# Power_micro_v3.net
KiCad netlist of a schematic drawn in Altium Designer
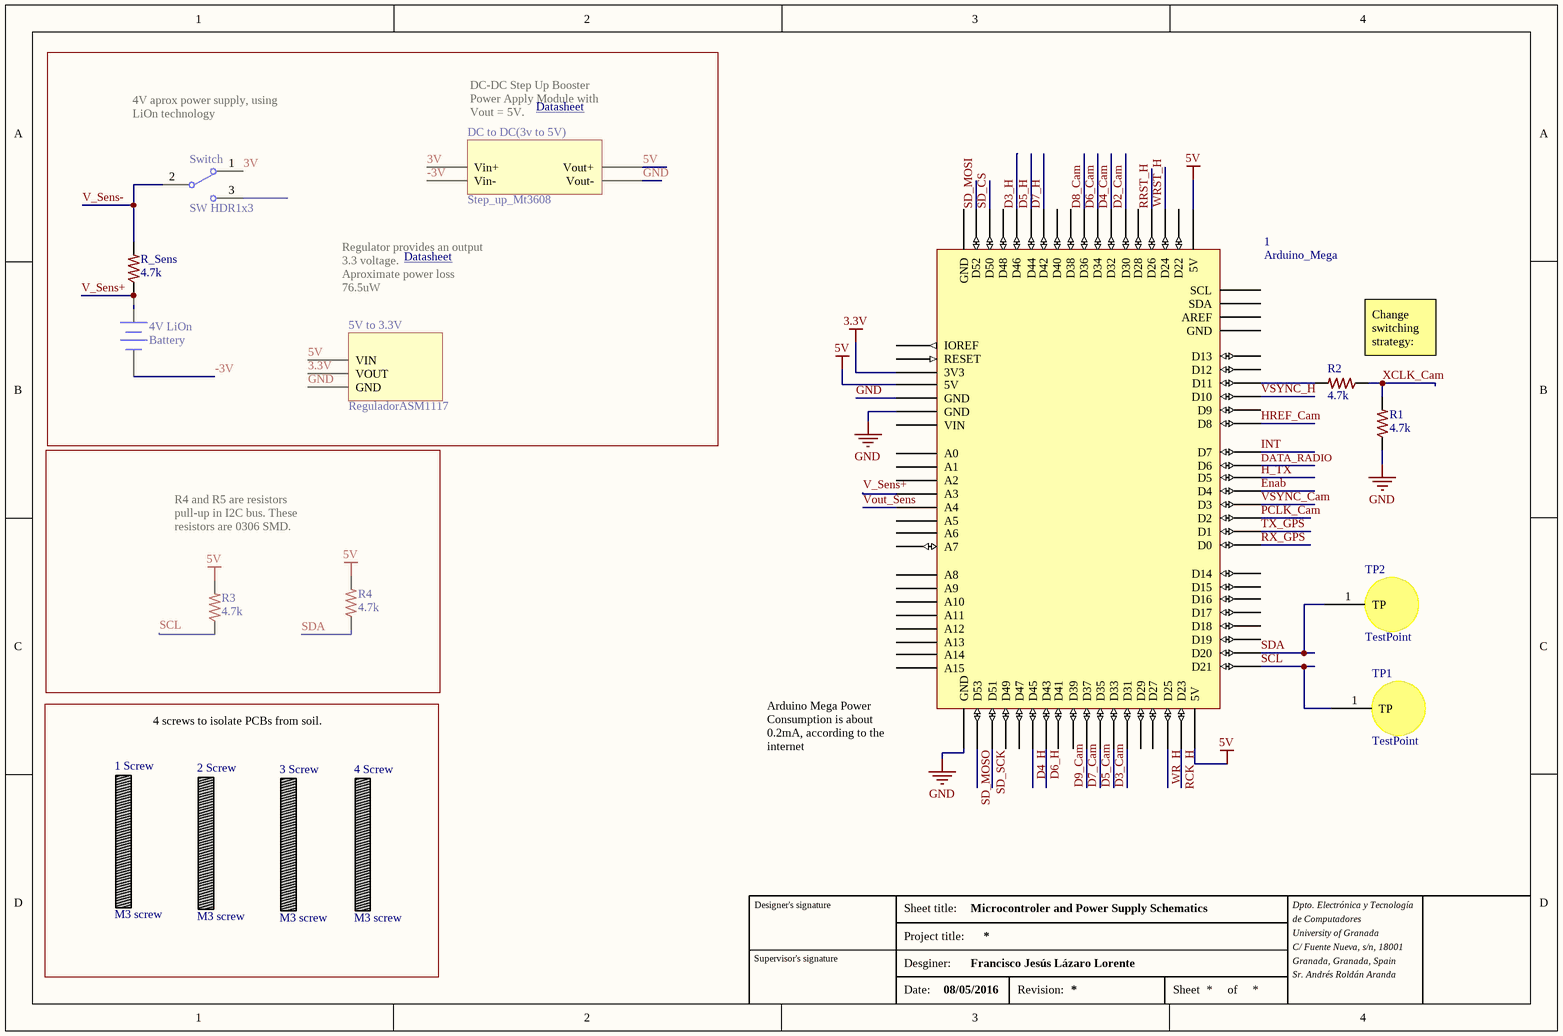
[diagram p0: Power_micro_v3.SchDoc]

(export (version "E")
  (design (tool "Eeschema 10.0.6"))
  (components
    (comp (ref "1")
      (value "Arduino_Mega")
      (footprint "Footprint-ArduinoMega-headers - named")
      (libsource (lib "Trackuino_Shield") (part "Arduino_Mega"))
    )
    (comp (ref "1 Screw")
      (value "M3 screw")
      (footprint "M3Screw")
      (libsource (lib "Schlib1") (part "M3 screw"))
    )
    (comp (ref "2 Screw")
      (value "M3 screw")
      (footprint "M3Screw")
      (libsource (lib "Schlib1") (part "M3 screw"))
    )
    (comp (ref "3 Screw")
      (value "M3 screw")
      (footprint "M3Screw")
      (libsource (lib "Schlib1") (part "M3 screw"))
    )
    (comp (ref "4 Screw")
      (value "M3 screw")
      (footprint "M3Screw")
      (libsource (lib "Schlib1") (part "M3 screw"))
    )
    (comp (ref "4V LiOn")
      (value "Battery")
      (footprint "BAT-2 - duplicate")
      (description "Multicell Battery")
      (fields (field (name "PUBLISHER") "Altium Limited"))
      (libsource (lib "Trackuino_Shield") (part "Battery"))
    )
    (comp (ref "5V to 3.3V")
      (value "ReguladorASM1117")
      (footprint "1X03 - ReguladorASM1117 - horizontal")
      (libsource (lib "Trackuino_Shield") (part "ReguladorASM1117"))
    )
    (comp (ref "DC to DC(3v to 5V)")
      (value "Step_up_Mt3608")
      (footprint "Step_up_Mt3608")
      (libsource (lib "Trackuino_Shield") (part "Step_up_Mt3608"))
    )
    (comp (ref "R1")
      (value "4.7k")
      (footprint "0805")
      (libsource (lib "Trackuino_Shield") (part "0805RESISTOR"))
    )
    (comp (ref "R2")
      (value "4.7k")
      (footprint "0805")
      (libsource (lib "Trackuino_Shield") (part "0805RESISTOR"))
    )
    (comp (ref "R3")
      (value "4.7k")
      (footprint "0805")
      (libsource (lib "Trackuino_Shield") (part "0805RESISTOR"))
    )
    (comp (ref "R4")
      (value "4.7k")
      (footprint "0805")
      (libsource (lib "Trackuino_Shield") (part "0805RESISTOR"))
    )
    (comp (ref "R_Sens")
      (value "4.7k")
      (footprint "0805")
      (libsource (lib "Trackuino_Shield") (part "0805RESISTOR"))
    )
    (comp (ref "Switch")
      (value "SW HDR1x3")
      (footprint "SWITCH3x1")
      (libsource (lib "Trackuino_Shield") (part "SW HDR1x3"))
    )
    (comp (ref "TP1")
      (value "TestPoint")
      (footprint "TestPoint")
      (libsource (lib "Trackuino_Shield") (part "TestPoint"))
    )
    (comp (ref "TP2")
      (value "TestPoint")
      (footprint "TestPoint")
      (libsource (lib "Trackuino_Shield") (part "TestPoint"))
    )
  )
  (nets
    (net (code "1") (name "/-3V") (class "Default")
      (node (ref "4V LiOn") (pin "GND") (pinfunction "-_GND") (pintype "passive"))
      (node (ref "DC to DC(3v to 5V)") (pin "VIN-") (pinfunction "Vin-_VIN-") (pintype "passive"))
    )
    (net (code "2") (name "/3V") (class "Default")
      (node (ref "DC to DC(3v to 5V)") (pin "VIN+") (pinfunction "Vin+_VIN+") (pintype "passive"))
      (node (ref "Switch") (pin "1") (pinfunction "NC1_1") (pintype "passive"))
    )
    (net (code "3") (name "/D2_Cam") (class "Default")
      (node (ref "1") (pin "D30") (pinfunction "D30_D30") (pintype "bidirectional"))
    )
    (net (code "4") (name "/D3_Cam") (class "Default")
      (node (ref "1") (pin "D31") (pinfunction "D31_D31") (pintype "bidirectional"))
    )
    (net (code "5") (name "/D3_H") (class "Default")
      (node (ref "1") (pin "D46") (pinfunction "D46_D46") (pintype "bidirectional"))
    )
    (net (code "6") (name "/D4_Cam") (class "Default")
      (node (ref "1") (pin "D32") (pinfunction "D32_D32") (pintype "bidirectional"))
    )
    (net (code "7") (name "/D4_H") (class "Default")
      (node (ref "1") (pin "D45") (pinfunction "D45_D45") (pintype "bidirectional"))
    )
    (net (code "8") (name "/D5_Cam") (class "Default")
      (node (ref "1") (pin "D33") (pinfunction "D33_D33") (pintype "bidirectional"))
    )
    (net (code "9") (name "/D5_H") (class "Default")
      (node (ref "1") (pin "D44") (pinfunction "D44_D44") (pintype "bidirectional"))
    )
    (net (code "10") (name "/D6_Cam") (class "Default")
      (node (ref "1") (pin "D34") (pinfunction "D34_D34") (pintype "bidirectional"))
    )
    (net (code "11") (name "/D6_H") (class "Default")
      (node (ref "1") (pin "D43") (pinfunction "D43_D43") (pintype "bidirectional"))
    )
    (net (code "12") (name "/D7_Cam") (class "Default")
      (node (ref "1") (pin "D35") (pinfunction "D35_D35") (pintype "bidirectional"))
    )
    (net (code "13") (name "/D7_H") (class "Default")
      (node (ref "1") (pin "D42") (pinfunction "D42_D42") (pintype "bidirectional"))
    )
    (net (code "14") (name "/D8_Cam") (class "Default")
      (node (ref "1") (pin "D36") (pinfunction "D36_D36") (pintype "bidirectional"))
    )
    (net (code "15") (name "/D9_Cam") (class "Default")
      (node (ref "1") (pin "D37") (pinfunction "D37_D37") (pintype "bidirectional"))
    )
    (net (code "16") (name "/DATA_RADIO") (class "Default")
      (node (ref "1") (pin "D6") (pinfunction "D6_D6") (pintype "bidirectional"))
    )
    (net (code "17") (name "/Enab") (class "Default")
      (node (ref "1") (pin "D4") (pinfunction "D4_D4") (pintype "bidirectional"))
    )
    (net (code "18") (name "/HREF_Cam") (class "Default")
      (node (ref "1") (pin "D8") (pinfunction "D8_D8") (pintype "bidirectional"))
    )
    (net (code "19") (name "/H_TX") (class "Default")
      (node (ref "1") (pin "D5") (pinfunction "D5_D5") (pintype "bidirectional"))
    )
    (net (code "20") (name "/INT") (class "Default")
      (node (ref "1") (pin "D7") (pinfunction "D7_D7") (pintype "bidirectional"))
    )
    (net (code "21") (name "/PCLK_Cam") (class "Default")
      (node (ref "1") (pin "D2") (pinfunction "D2_D2") (pintype "bidirectional"))
    )
    (net (code "22") (name "/RCK_H") (class "Default")
      (node (ref "1") (pin "D23") (pinfunction "D23_D23") (pintype "bidirectional"))
    )
    (net (code "23") (name "/RRST_H") (class "Default")
      (node (ref "1") (pin "D26") (pinfunction "D26_D26") (pintype "bidirectional"))
    )
    (net (code "24") (name "/RX_GPS") (class "Default")
      (node (ref "1") (pin "D0") (pinfunction "D0_D0") (pintype "bidirectional"))
    )
    (net (code "25") (name "/SCL") (class "Default")
      (node (ref "1") (pin "D21") (pinfunction "D21_D21") (pintype "bidirectional"))
      (node (ref "R3") (pin "1") (pinfunction "1_1") (pintype "passive"))
      (node (ref "TP1") (pin "1") (pinfunction "TP_1") (pintype "passive"))
    )
    (net (code "26") (name "/SDA") (class "Default")
      (node (ref "1") (pin "D20") (pinfunction "D20_D20") (pintype "bidirectional"))
      (node (ref "R4") (pin "1") (pinfunction "1_1") (pintype "passive"))
      (node (ref "TP2") (pin "1") (pinfunction "TP_1") (pintype "passive"))
    )
    (net (code "27") (name "/SD_CS") (class "Default")
      (node (ref "1") (pin "D50") (pinfunction "D50_D50") (pintype "bidirectional"))
    )
    (net (code "28") (name "/SD_MOSI") (class "Default")
      (node (ref "1") (pin "D52") (pinfunction "D52_D52") (pintype "bidirectional"))
    )
    (net (code "29") (name "/SD_MOSO") (class "Default")
      (node (ref "1") (pin "D53") (pinfunction "D53_D53") (pintype "bidirectional"))
    )
    (net (code "30") (name "/SD_SCK") (class "Default")
      (node (ref "1") (pin "D51") (pinfunction "D51_D51") (pintype "bidirectional"))
    )
    (net (code "31") (name "/TX_GPS") (class "Default")
      (node (ref "1") (pin "D1") (pinfunction "D1_D1") (pintype "bidirectional"))
    )
    (net (code "32") (name "/VSYNC_Cam") (class "Default")
      (node (ref "1") (pin "D3") (pinfunction "D3_D3") (pintype "bidirectional"))
    )
    (net (code "33") (name "/VSYNC_H") (class "Default")
      (node (ref "1") (pin "D10") (pinfunction "D10_D10") (pintype "bidirectional"))
    )
    (net (code "34") (name "/V_Sens+") (class "Default")
      (node (ref "1") (pin "A3") (pinfunction "A3_A3") (pintype "tri_state"))
      (node (ref "4V LiOn") (pin "VCC") (pinfunction "+_VCC") (pintype "passive"))
      (node (ref "R_Sens") (pin "1") (pinfunction "1_1") (pintype "passive"))
    )
    (net (code "35") (name "/V_Sens-") (class "Default")
      (node (ref "R_Sens") (pin "2") (pinfunction "2_2") (pintype "passive"))
      (node (ref "Switch") (pin "2") (pinfunction "COMMON1_2") (pintype "passive"))
    )
    (net (code "36") (name "/Vout_Sens") (class "Default")
      (node (ref "1") (pin "A4") (pinfunction "A4_A4") (pintype "tri_state"))
    )
    (net (code "37") (name "/WRST_H") (class "Default")
      (node (ref "1") (pin "D24") (pinfunction "D24_D24") (pintype "bidirectional"))
    )
    (net (code "38") (name "/WR_H") (class "Default")
      (node (ref "1") (pin "D25") (pinfunction "D25_D25") (pintype "bidirectional"))
    )
    (net (code "39") (name "/XCLK_Cam") (class "Default")
      (node (ref "R1") (pin "2") (pinfunction "2_2") (pintype "passive"))
      (node (ref "R2") (pin "1") (pinfunction "1_1") (pintype "passive"))
    )
    (net (code "40") (name "3.3V") (class "Default")
      (node (ref "1") (pin "3V3") (pinfunction "3V3_3V3") (pintype "power_in"))
      (node (ref "5V to 3.3V") (pin "VOUT") (pinfunction "VOUT_VOUT") (pintype "power_in"))
    )
    (net (code "41") (name "5V") (class "Default")
      (node (ref "1") (pin "5V_BB") (pinfunction "5V_5V_BB") (pintype "power_in"))
      (node (ref "1") (pin "5V_BT") (pinfunction "5V_5V_BT") (pintype "power_in"))
      (node (ref "1") (pin "5V_TL") (pinfunction "5V_5V_TL") (pintype "power_in"))
      (node (ref "5V to 3.3V") (pin "VIN") (pinfunction "VIN_VIN") (pintype "power_in"))
      (node (ref "DC to DC(3v to 5V)") (pin "VOUT+") (pinfunction "Vout+_VOUT+") (pintype "passive"))
      (node (ref "R3") (pin "2") (pinfunction "2_2") (pintype "passive"))
      (node (ref "R4") (pin "2") (pinfunction "2_2") (pintype "passive"))
    )
    (net (code "42") (name "GND") (class "Default")
      (node (ref "1") (pin "GND_BB") (pinfunction "GND_GND_BB") (pintype "power_in"))
      (node (ref "1") (pin "GND_TLB") (pinfunction "GND_GND_TLB") (pintype "power_in"))
      (node (ref "1") (pin "GND_TLT") (pinfunction "GND_GND_TLT") (pintype "power_in"))
      (node (ref "5V to 3.3V") (pin "GND") (pinfunction "GND_GND") (pintype "power_in"))
      (node (ref "DC to DC(3v to 5V)") (pin "VOUT-") (pinfunction "Vout-_VOUT-") (pintype "passive"))
      (node (ref "R1") (pin "1") (pinfunction "1_1") (pintype "passive"))
    )
    (net (code "43") (name "Net-(1-PadD11)") (class "Default")
      (node (ref "1") (pin "D11") (pinfunction "D11_D11") (pintype "bidirectional"))
      (node (ref "R2") (pin "2") (pinfunction "2_2") (pintype "passive"))
    )
    (net (code "44") (name "unconnected-(1-GND-PadGND_BT)") (class "Default")
      (node (ref "1") (pin "GND_BT") (pinfunction "GND_GND_BT") (pintype "power_in"))
    )
    (net (code "45") (name "unconnected-(1-GND-PadGND_TR)") (class "Default")
      (node (ref "1") (pin "GND_TR") (pinfunction "GND_GND_TR") (pintype "open_collector"))
    )
    (net (code "46") (name "unconnected-(1-PadA0)") (class "Default")
      (node (ref "1") (pin "A0") (pinfunction "A0_A0") (pintype "tri_state"))
    )
    (net (code "47") (name "unconnected-(1-PadA1)") (class "Default")
      (node (ref "1") (pin "A1") (pinfunction "A1_A1") (pintype "tri_state"))
    )
    (net (code "48") (name "unconnected-(1-PadA2)") (class "Default")
      (node (ref "1") (pin "A2") (pinfunction "A2_A2") (pintype "tri_state"))
    )
    (net (code "49") (name "unconnected-(1-PadA5)") (class "Default")
      (node (ref "1") (pin "A5") (pinfunction "A5_A5") (pintype "tri_state"))
    )
    (net (code "50") (name "unconnected-(1-PadA6)") (class "Default")
      (node (ref "1") (pin "A6") (pinfunction "A6_A6") (pintype "tri_state"))
    )
    (net (code "51") (name "unconnected-(1-PadA7)") (class "Default")
      (node (ref "1") (pin "A7") (pinfunction "A7_A7") (pintype "bidirectional"))
    )
    (net (code "52") (name "unconnected-(1-PadA8)") (class "Default")
      (node (ref "1") (pin "A8") (pinfunction "A8_A8") (pintype "tri_state"))
    )
    (net (code "53") (name "unconnected-(1-PadA9)") (class "Default")
      (node (ref "1") (pin "A9") (pinfunction "A9_A9") (pintype "tri_state"))
    )
    (net (code "54") (name "unconnected-(1-PadA10)") (class "Default")
      (node (ref "1") (pin "A10") (pinfunction "A10_A10") (pintype "tri_state"))
    )
    (net (code "55") (name "unconnected-(1-PadA11)") (class "Default")
      (node (ref "1") (pin "A11") (pinfunction "A11_A11") (pintype "tri_state"))
    )
    (net (code "56") (name "unconnected-(1-PadA12)") (class "Default")
      (node (ref "1") (pin "A12") (pinfunction "A12_A12") (pintype "tri_state"))
    )
    (net (code "57") (name "unconnected-(1-PadA13)") (class "Default")
      (node (ref "1") (pin "A13") (pinfunction "A13_A13") (pintype "tri_state"))
    )
    (net (code "58") (name "unconnected-(1-PadA14)") (class "Default")
      (node (ref "1") (pin "A14") (pinfunction "A14_A14") (pintype "tri_state"))
    )
    (net (code "59") (name "unconnected-(1-PadA15)") (class "Default")
      (node (ref "1") (pin "A15") (pinfunction "A15_A15") (pintype "tri_state"))
    )
    (net (code "60") (name "unconnected-(1-PadAREF)") (class "Default")
      (node (ref "1") (pin "AREF") (pinfunction "AREF_AREF") (pintype "tri_state"))
    )
    (net (code "61") (name "unconnected-(1-PadD9)") (class "Default")
      (node (ref "1") (pin "D9") (pinfunction "D9_D9") (pintype "bidirectional"))
    )
    (net (code "62") (name "unconnected-(1-PadD12)") (class "Default")
      (node (ref "1") (pin "D12") (pinfunction "D12_D12") (pintype "bidirectional"))
    )
    (net (code "63") (name "unconnected-(1-PadD13)") (class "Default")
      (node (ref "1") (pin "D13") (pinfunction "D13_D13") (pintype "bidirectional"))
    )
    (net (code "64") (name "unconnected-(1-PadD14)") (class "Default")
      (node (ref "1") (pin "D14") (pinfunction "D14_D14") (pintype "bidirectional"))
    )
    (net (code "65") (name "unconnected-(1-PadD15)") (class "Default")
      (node (ref "1") (pin "D15") (pinfunction "D15_D15") (pintype "bidirectional"))
    )
    (net (code "66") (name "unconnected-(1-PadD16)") (class "Default")
      (node (ref "1") (pin "D16") (pinfunction "D16_D16") (pintype "bidirectional"))
    )
    (net (code "67") (name "unconnected-(1-PadD17)") (class "Default")
      (node (ref "1") (pin "D17") (pinfunction "D17_D17") (pintype "bidirectional"))
    )
    (net (code "68") (name "unconnected-(1-PadD18)") (class "Default")
      (node (ref "1") (pin "D18") (pinfunction "D18_D18") (pintype "bidirectional"))
    )
    (net (code "69") (name "unconnected-(1-PadD19)") (class "Default")
      (node (ref "1") (pin "D19") (pinfunction "D19_D19") (pintype "bidirectional"))
    )
    (net (code "70") (name "unconnected-(1-PadD22)") (class "Default")
      (node (ref "1") (pin "D22") (pinfunction "D22_D22") (pintype "bidirectional"))
    )
    (net (code "71") (name "unconnected-(1-PadD27)") (class "Default")
      (node (ref "1") (pin "D27") (pinfunction "D27_D27") (pintype "bidirectional"))
    )
    (net (code "72") (name "unconnected-(1-PadD28)") (class "Default")
      (node (ref "1") (pin "D28") (pinfunction "D28_D28") (pintype "bidirectional"))
    )
    (net (code "73") (name "unconnected-(1-PadD29)") (class "Default")
      (node (ref "1") (pin "D29") (pinfunction "D29_D29") (pintype "bidirectional"))
    )
    (net (code "74") (name "unconnected-(1-PadD38)") (class "Default")
      (node (ref "1") (pin "D38") (pinfunction "D38_D38") (pintype "bidirectional"))
    )
    (net (code "75") (name "unconnected-(1-PadD39)") (class "Default")
      (node (ref "1") (pin "D39") (pinfunction "D39_D39") (pintype "bidirectional"))
    )
    (net (code "76") (name "unconnected-(1-PadD40)") (class "Default")
      (node (ref "1") (pin "D40") (pinfunction "D40_D40") (pintype "bidirectional"))
    )
    (net (code "77") (name "unconnected-(1-PadD41)") (class "Default")
      (node (ref "1") (pin "D41") (pinfunction "D41_D41") (pintype "bidirectional"))
    )
    (net (code "78") (name "unconnected-(1-PadD47)") (class "Default")
      (node (ref "1") (pin "D47") (pinfunction "D47_D47") (pintype "bidirectional"))
    )
    (net (code "79") (name "unconnected-(1-PadD48)") (class "Default")
      (node (ref "1") (pin "D48") (pinfunction "D48_D48") (pintype "bidirectional"))
    )
    (net (code "80") (name "unconnected-(1-PadD49)") (class "Default")
      (node (ref "1") (pin "D49") (pinfunction "D49_D49") (pintype "bidirectional"))
    )
    (net (code "81") (name "unconnected-(1-PadIOREF)") (class "Default")
      (node (ref "1") (pin "IOREF") (pinfunction "IOREF_IOREF") (pintype "output"))
    )
    (net (code "82") (name "unconnected-(1-PadRESET)") (class "Default")
      (node (ref "1") (pin "RESET") (pinfunction "RESET_RESET") (pintype "input"))
    )
    (net (code "83") (name "unconnected-(1-PadSCL)") (class "Default")
      (node (ref "1") (pin "SCL") (pinfunction "SCL_SCL") (pintype "open_collector"))
    )
    (net (code "84") (name "unconnected-(1-PadSDA)") (class "Default")
      (node (ref "1") (pin "SDA") (pinfunction "SDA_SDA") (pintype "open_collector"))
    )
    (net (code "85") (name "unconnected-(1-PadVIN)") (class "Default")
      (node (ref "1") (pin "VIN") (pinfunction "VIN_VIN") (pintype "power_in"))
    )
    (net (code "86") (name "unconnected-(Switch-NO1-Pad3)") (class "Default")
      (node (ref "Switch") (pin "3") (pinfunction "NO1_3") (pintype "passive"))
    )
  )
)
